# breakout.net
KiCad netlist of a schematic drawn in EAGLE
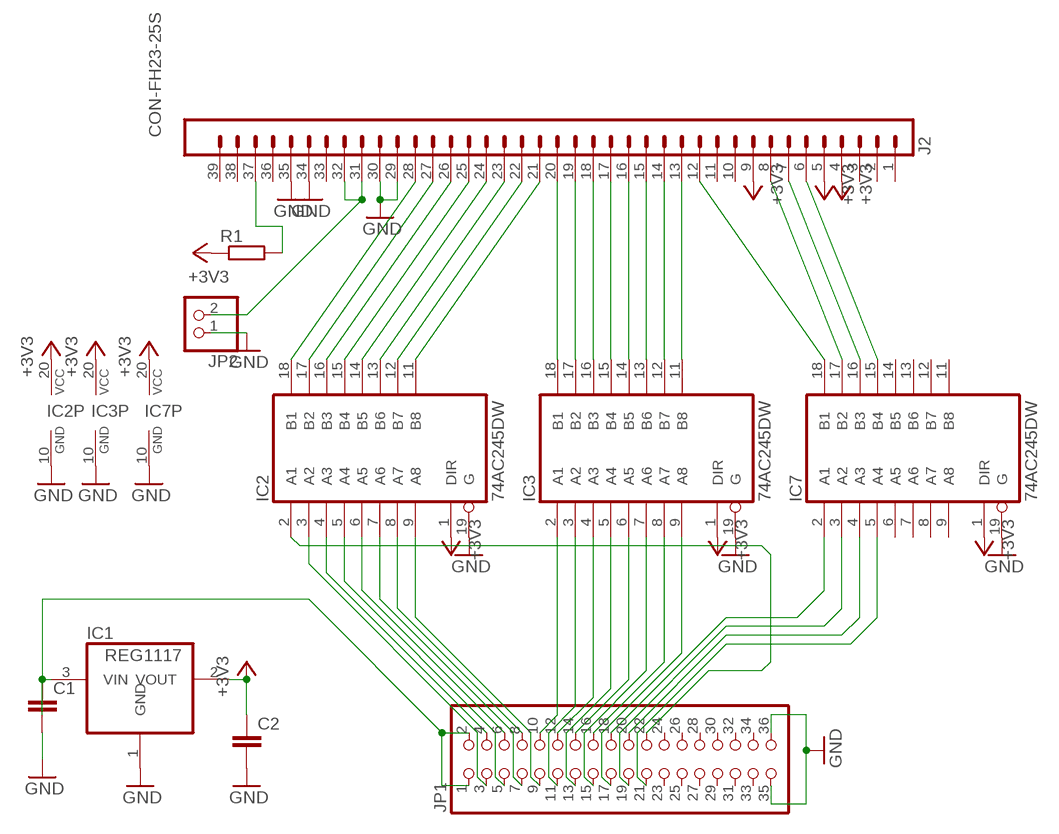
[diagram p0: schematic, sheet 1]

(export (version "E")
  (design (tool "Eeschema 10.0.6"))
  (components
    (comp (ref "C1")
      (value "C-EUC0805")
      (footprint "eagle-import:C0805")
      (libsource (lib "eagle-import") (part "C-EUC0805"))
    )
    (comp (ref "C2")
      (value "C-EUC0805")
      (footprint "eagle-import:C0805")
      (libsource (lib "eagle-import") (part "C-EUC0805"))
    )
    (comp (ref "IC1")
      (value "REG1117")
      (footprint "eagle-import:SOT223")
      (libsource (lib "eagle-import") (part "REG1117"))
    )
    (comp (ref "IC2")
      (value "74AC245DW")
      (footprint "eagle-import:SO20W")
      (libsource (lib "eagle-import") (part "74245DWAC"))
    )
    (comp (ref "IC3")
      (value "74AC245DW")
      (footprint "eagle-import:SO20W")
      (libsource (lib "eagle-import") (part "74245DWAC"))
    )
    (comp (ref "IC7")
      (value "74AC245DW")
      (footprint "eagle-import:SO20W")
      (libsource (lib "eagle-import") (part "74245DWAC"))
    )
    (comp (ref "J2")
      (value "CON-FH23-25S")
      (footprint "eagle-import:FH23-25S")
      (libsource (lib "eagle-import") (part "CON-FH23-25S"))
    )
    (comp (ref "JP1")
      (value "PINHD-2X18")
      (footprint "eagle-import:2X18")
      (libsource (lib "eagle-import") (part "PINHD-2X18"))
    )
    (comp (ref "JP2")
      (value "PINHD-1X2")
      (footprint "eagle-import:1X02")
      (libsource (lib "eagle-import") (part "PINHD-1X2"))
    )
    (comp (ref "R1")
      (value "R-EU_R0805")
      (footprint "eagle-import:R0805")
      (libsource (lib "eagle-import") (part "R-EU_R0805"))
    )
  )
  (nets
    (net (code "1") (name "+3V3") (class "Default")
      (node (ref "C2") (pin "1") (pinfunction "1_1") (pintype "passive"))
      (node (ref "IC1") (pin "2") (pinfunction "VOUT_2") (pintype "output"))
      (node (ref "IC2") (pin "1") (pinfunction "DIR_1") (pintype "input"))
      (node (ref "IC2") (pin "20") (pinfunction "VCC_20") (pintype "power_in"))
      (node (ref "IC3") (pin "1") (pinfunction "DIR_1") (pintype "input"))
      (node (ref "IC3") (pin "20") (pinfunction "VCC_20") (pintype "power_in"))
      (node (ref "IC7") (pin "1") (pinfunction "DIR_1") (pintype "input"))
      (node (ref "IC7") (pin "20") (pinfunction "VCC_20") (pintype "power_in"))
      (node (ref "J2") (pin "4") (pinfunction "4_4") (pintype "passive"))
      (node (ref "J2") (pin "5") (pinfunction "5_5") (pintype "passive"))
      (node (ref "J2") (pin "9") (pinfunction "9_9") (pintype "passive"))
      (node (ref "R1") (pin "1") (pinfunction "1_1") (pintype "passive"))
    )
    (net (code "2") (name "GND") (class "Default")
      (node (ref "C1") (pin "2") (pinfunction "2_2") (pintype "passive"))
      (node (ref "C2") (pin "2") (pinfunction "2_2") (pintype "passive"))
      (node (ref "IC1") (pin "1") (pinfunction "GND_1") (pintype "power_in"))
      (node (ref "IC2") (pin "10") (pinfunction "GND_10") (pintype "power_in"))
      (node (ref "IC2") (pin "19") (pinfunction "G_19") (pintype "input"))
      (node (ref "IC3") (pin "10") (pinfunction "GND_10") (pintype "power_in"))
      (node (ref "IC3") (pin "19") (pinfunction "G_19") (pintype "input"))
      (node (ref "IC7") (pin "10") (pinfunction "GND_10") (pintype "power_in"))
      (node (ref "IC7") (pin "19") (pinfunction "G_19") (pintype "input"))
      (node (ref "J2") (pin "29") (pinfunction "29_29") (pintype "passive"))
      (node (ref "J2") (pin "30") (pinfunction "30_30") (pintype "passive"))
      (node (ref "J2") (pin "34") (pinfunction "34_34") (pintype "passive"))
      (node (ref "J2") (pin "35") (pinfunction "35_35") (pintype "passive"))
      (node (ref "JP1") (pin "35") (pinfunction "35_35") (pintype "passive"))
      (node (ref "JP1") (pin "36") (pinfunction "36_36") (pintype "passive"))
      (node (ref "JP2") (pin "1") (pinfunction "1_1") (pintype "passive"))
    )
    (net (code "3") (name "Net-(IC1-VIN)") (class "Default")
      (node (ref "C1") (pin "1") (pinfunction "1_1") (pintype "passive"))
      (node (ref "IC1") (pin "3") (pinfunction "VIN_3") (pintype "input"))
      (node (ref "JP1") (pin "1") (pinfunction "1_1") (pintype "passive"))
      (node (ref "JP1") (pin "2") (pinfunction "2_2") (pintype "passive"))
    )
    (net (code "4") (name "Net-(IC2A-A1)") (class "Default")
      (node (ref "IC2") (pin "2") (pinfunction "A1_2") (pintype "bidirectional"))
      (node (ref "JP1") (pin "22") (pinfunction "22_22") (pintype "passive"))
    )
    (net (code "5") (name "Net-(IC2A-A2)") (class "Default")
      (node (ref "IC2") (pin "3") (pinfunction "A2_3") (pintype "bidirectional"))
      (node (ref "JP1") (pin "3") (pinfunction "3_3") (pintype "passive"))
    )
    (net (code "6") (name "Net-(IC2A-A3)") (class "Default")
      (node (ref "IC2") (pin "4") (pinfunction "A3_4") (pintype "bidirectional"))
      (node (ref "JP1") (pin "4") (pinfunction "4_4") (pintype "passive"))
    )
    (net (code "7") (name "Net-(IC2A-A4)") (class "Default")
      (node (ref "IC2") (pin "5") (pinfunction "A4_5") (pintype "bidirectional"))
      (node (ref "JP1") (pin "5") (pinfunction "5_5") (pintype "passive"))
    )
    (net (code "8") (name "Net-(IC2A-A5)") (class "Default")
      (node (ref "IC2") (pin "6") (pinfunction "A5_6") (pintype "bidirectional"))
      (node (ref "JP1") (pin "6") (pinfunction "6_6") (pintype "passive"))
    )
    (net (code "9") (name "Net-(IC2A-A6)") (class "Default")
      (node (ref "IC2") (pin "7") (pinfunction "A6_7") (pintype "bidirectional"))
      (node (ref "JP1") (pin "7") (pinfunction "7_7") (pintype "passive"))
    )
    (net (code "10") (name "Net-(IC2A-A7)") (class "Default")
      (node (ref "IC2") (pin "8") (pinfunction "A7_8") (pintype "bidirectional"))
      (node (ref "JP1") (pin "8") (pinfunction "8_8") (pintype "passive"))
    )
    (net (code "11") (name "Net-(IC2A-A8)") (class "Default")
      (node (ref "IC2") (pin "9") (pinfunction "A8_9") (pintype "bidirectional"))
      (node (ref "JP1") (pin "9") (pinfunction "9_9") (pintype "passive"))
    )
    (net (code "12") (name "Net-(IC2A-B1)") (class "Default")
      (node (ref "IC2") (pin "18") (pinfunction "B1_18") (pintype "bidirectional"))
      (node (ref "J2") (pin "28") (pinfunction "28_28") (pintype "passive"))
    )
    (net (code "13") (name "Net-(IC2A-B2)") (class "Default")
      (node (ref "IC2") (pin "17") (pinfunction "B2_17") (pintype "bidirectional"))
      (node (ref "J2") (pin "27") (pinfunction "27_27") (pintype "passive"))
    )
    (net (code "14") (name "Net-(IC2A-B3)") (class "Default")
      (node (ref "IC2") (pin "16") (pinfunction "B3_16") (pintype "bidirectional"))
      (node (ref "J2") (pin "26") (pinfunction "26_26") (pintype "passive"))
    )
    (net (code "15") (name "Net-(IC2A-B4)") (class "Default")
      (node (ref "IC2") (pin "15") (pinfunction "B4_15") (pintype "bidirectional"))
      (node (ref "J2") (pin "25") (pinfunction "25_25") (pintype "passive"))
    )
    (net (code "16") (name "Net-(IC2A-B5)") (class "Default")
      (node (ref "IC2") (pin "14") (pinfunction "B5_14") (pintype "bidirectional"))
      (node (ref "J2") (pin "24") (pinfunction "24_24") (pintype "passive"))
    )
    (net (code "17") (name "Net-(IC2A-B6)") (class "Default")
      (node (ref "IC2") (pin "13") (pinfunction "B6_13") (pintype "bidirectional"))
      (node (ref "J2") (pin "23") (pinfunction "23_23") (pintype "passive"))
    )
    (net (code "18") (name "Net-(IC2A-B7)") (class "Default")
      (node (ref "IC2") (pin "12") (pinfunction "B7_12") (pintype "bidirectional"))
      (node (ref "J2") (pin "22") (pinfunction "22_22") (pintype "passive"))
    )
    (net (code "19") (name "Net-(IC2A-B8)") (class "Default")
      (node (ref "IC2") (pin "11") (pinfunction "B8_11") (pintype "bidirectional"))
      (node (ref "J2") (pin "21") (pinfunction "21_21") (pintype "passive"))
    )
    (net (code "20") (name "Net-(IC3A-A1)") (class "Default")
      (node (ref "IC3") (pin "2") (pinfunction "A1_2") (pintype "bidirectional"))
      (node (ref "JP1") (pin "10") (pinfunction "10_10") (pintype "passive"))
    )
    (net (code "21") (name "Net-(IC3A-A2)") (class "Default")
      (node (ref "IC3") (pin "3") (pinfunction "A2_3") (pintype "bidirectional"))
      (node (ref "JP1") (pin "11") (pinfunction "11_11") (pintype "passive"))
    )
    (net (code "22") (name "Net-(IC3A-A3)") (class "Default")
      (node (ref "IC3") (pin "4") (pinfunction "A3_4") (pintype "bidirectional"))
      (node (ref "JP1") (pin "12") (pinfunction "12_12") (pintype "passive"))
    )
    (net (code "23") (name "Net-(IC3A-A4)") (class "Default")
      (node (ref "IC3") (pin "5") (pinfunction "A4_5") (pintype "bidirectional"))
      (node (ref "JP1") (pin "13") (pinfunction "13_13") (pintype "passive"))
    )
    (net (code "24") (name "Net-(IC3A-A5)") (class "Default")
      (node (ref "IC3") (pin "6") (pinfunction "A5_6") (pintype "bidirectional"))
      (node (ref "JP1") (pin "14") (pinfunction "14_14") (pintype "passive"))
    )
    (net (code "25") (name "Net-(IC3A-A6)") (class "Default")
      (node (ref "IC3") (pin "7") (pinfunction "A6_7") (pintype "bidirectional"))
      (node (ref "JP1") (pin "15") (pinfunction "15_15") (pintype "passive"))
    )
    (net (code "26") (name "Net-(IC3A-A7)") (class "Default")
      (node (ref "IC3") (pin "8") (pinfunction "A7_8") (pintype "bidirectional"))
      (node (ref "JP1") (pin "16") (pinfunction "16_16") (pintype "passive"))
    )
    (net (code "27") (name "Net-(IC3A-A8)") (class "Default")
      (node (ref "IC3") (pin "9") (pinfunction "A8_9") (pintype "bidirectional"))
      (node (ref "JP1") (pin "17") (pinfunction "17_17") (pintype "passive"))
    )
    (net (code "28") (name "Net-(IC3A-B1)") (class "Default")
      (node (ref "IC3") (pin "18") (pinfunction "B1_18") (pintype "bidirectional"))
      (node (ref "J2") (pin "20") (pinfunction "20_20") (pintype "passive"))
    )
    (net (code "29") (name "Net-(IC3A-B2)") (class "Default")
      (node (ref "IC3") (pin "17") (pinfunction "B2_17") (pintype "bidirectional"))
      (node (ref "J2") (pin "19") (pinfunction "19_19") (pintype "passive"))
    )
    (net (code "30") (name "Net-(IC3A-B3)") (class "Default")
      (node (ref "IC3") (pin "16") (pinfunction "B3_16") (pintype "bidirectional"))
      (node (ref "J2") (pin "18") (pinfunction "18_18") (pintype "passive"))
    )
    (net (code "31") (name "Net-(IC3A-B4)") (class "Default")
      (node (ref "IC3") (pin "15") (pinfunction "B4_15") (pintype "bidirectional"))
      (node (ref "J2") (pin "17") (pinfunction "17_17") (pintype "passive"))
    )
    (net (code "32") (name "Net-(IC3A-B5)") (class "Default")
      (node (ref "IC3") (pin "14") (pinfunction "B5_14") (pintype "bidirectional"))
      (node (ref "J2") (pin "16") (pinfunction "16_16") (pintype "passive"))
    )
    (net (code "33") (name "Net-(IC3A-B6)") (class "Default")
      (node (ref "IC3") (pin "13") (pinfunction "B6_13") (pintype "bidirectional"))
      (node (ref "J2") (pin "15") (pinfunction "15_15") (pintype "passive"))
    )
    (net (code "34") (name "Net-(IC3A-B7)") (class "Default")
      (node (ref "IC3") (pin "12") (pinfunction "B7_12") (pintype "bidirectional"))
      (node (ref "J2") (pin "14") (pinfunction "14_14") (pintype "passive"))
    )
    (net (code "35") (name "Net-(IC3A-B8)") (class "Default")
      (node (ref "IC3") (pin "11") (pinfunction "B8_11") (pintype "bidirectional"))
      (node (ref "J2") (pin "13") (pinfunction "13_13") (pintype "passive"))
    )
    (net (code "36") (name "Net-(IC7A-A1)") (class "Default")
      (node (ref "IC7") (pin "2") (pinfunction "A1_2") (pintype "bidirectional"))
      (node (ref "JP1") (pin "18") (pinfunction "18_18") (pintype "passive"))
    )
    (net (code "37") (name "Net-(IC7A-A2)") (class "Default")
      (node (ref "IC7") (pin "3") (pinfunction "A2_3") (pintype "bidirectional"))
      (node (ref "JP1") (pin "19") (pinfunction "19_19") (pintype "passive"))
    )
    (net (code "38") (name "Net-(IC7A-A3)") (class "Default")
      (node (ref "IC7") (pin "4") (pinfunction "A3_4") (pintype "bidirectional"))
      (node (ref "JP1") (pin "20") (pinfunction "20_20") (pintype "passive"))
    )
    (net (code "39") (name "Net-(IC7A-A4)") (class "Default")
      (node (ref "IC7") (pin "5") (pinfunction "A4_5") (pintype "bidirectional"))
      (node (ref "JP1") (pin "21") (pinfunction "21_21") (pintype "passive"))
    )
    (net (code "40") (name "Net-(IC7A-B1)") (class "Default")
      (node (ref "IC7") (pin "18") (pinfunction "B1_18") (pintype "bidirectional"))
      (node (ref "J2") (pin "12") (pinfunction "12_12") (pintype "passive"))
    )
    (net (code "41") (name "Net-(IC7A-B2)") (class "Default")
      (node (ref "IC7") (pin "17") (pinfunction "B2_17") (pintype "bidirectional"))
      (node (ref "J2") (pin "8") (pinfunction "8_8") (pintype "passive"))
    )
    (net (code "42") (name "Net-(IC7A-B3)") (class "Default")
      (node (ref "IC7") (pin "16") (pinfunction "B3_16") (pintype "bidirectional"))
      (node (ref "J2") (pin "7") (pinfunction "7_7") (pintype "passive"))
    )
    (net (code "43") (name "Net-(IC7A-B4)") (class "Default")
      (node (ref "IC7") (pin "15") (pinfunction "B4_15") (pintype "bidirectional"))
      (node (ref "J2") (pin "6") (pinfunction "6_6") (pintype "passive"))
    )
    (net (code "44") (name "Net-(J2-Pad31)") (class "Default")
      (node (ref "J2") (pin "31") (pinfunction "31_31") (pintype "passive"))
      (node (ref "J2") (pin "32") (pinfunction "32_32") (pintype "passive"))
      (node (ref "JP2") (pin "2") (pinfunction "2_2") (pintype "passive"))
    )
    (net (code "45") (name "Net-(J2-Pad37)") (class "Default")
      (node (ref "J2") (pin "37") (pinfunction "37_37") (pintype "passive"))
      (node (ref "R1") (pin "2") (pinfunction "2_2") (pintype "passive"))
    )
    (net (code "46") (name "unconnected-(IC7A-A5-Pad6)") (class "Default")
      (node (ref "IC7") (pin "6") (pinfunction "A5_6") (pintype "bidirectional"))
    )
    (net (code "47") (name "unconnected-(IC7A-A6-Pad7)") (class "Default")
      (node (ref "IC7") (pin "7") (pinfunction "A6_7") (pintype "bidirectional"))
    )
    (net (code "48") (name "unconnected-(IC7A-A7-Pad8)") (class "Default")
      (node (ref "IC7") (pin "8") (pinfunction "A7_8") (pintype "bidirectional"))
    )
    (net (code "49") (name "unconnected-(IC7A-A8-Pad9)") (class "Default")
      (node (ref "IC7") (pin "9") (pinfunction "A8_9") (pintype "bidirectional"))
    )
    (net (code "50") (name "unconnected-(IC7A-B5-Pad14)") (class "Default")
      (node (ref "IC7") (pin "14") (pinfunction "B5_14") (pintype "bidirectional"))
    )
    (net (code "51") (name "unconnected-(IC7A-B6-Pad13)") (class "Default")
      (node (ref "IC7") (pin "13") (pinfunction "B6_13") (pintype "bidirectional"))
    )
    (net (code "52") (name "unconnected-(IC7A-B7-Pad12)") (class "Default")
      (node (ref "IC7") (pin "12") (pinfunction "B7_12") (pintype "bidirectional"))
    )
    (net (code "53") (name "unconnected-(IC7A-B8-Pad11)") (class "Default")
      (node (ref "IC7") (pin "11") (pinfunction "B8_11") (pintype "bidirectional"))
    )
    (net (code "54") (name "unconnected-(J2-Pad1)") (class "Default")
      (node (ref "J2") (pin "1") (pinfunction "1_1") (pintype "passive"))
    )
    (net (code "55") (name "unconnected-(J2-Pad2)") (class "Default")
      (node (ref "J2") (pin "2") (pinfunction "2_2") (pintype "passive"))
    )
    (net (code "56") (name "unconnected-(J2-Pad3)") (class "Default")
      (node (ref "J2") (pin "3") (pinfunction "3_3") (pintype "passive"))
    )
    (net (code "57") (name "unconnected-(J2-Pad10)") (class "Default")
      (node (ref "J2") (pin "10") (pinfunction "10_10") (pintype "passive"))
    )
    (net (code "58") (name "unconnected-(J2-Pad11)") (class "Default")
      (node (ref "J2") (pin "11") (pinfunction "11_11") (pintype "passive"))
    )
    (net (code "59") (name "unconnected-(J2-Pad33)") (class "Default")
      (node (ref "J2") (pin "33") (pinfunction "33_33") (pintype "passive"))
    )
    (net (code "60") (name "unconnected-(J2-Pad36)") (class "Default")
      (node (ref "J2") (pin "36") (pinfunction "36_36") (pintype "passive"))
    )
    (net (code "61") (name "unconnected-(J2-Pad38)") (class "Default")
      (node (ref "J2") (pin "38") (pinfunction "38_38") (pintype "passive"))
    )
    (net (code "62") (name "unconnected-(J2-Pad39)") (class "Default")
      (node (ref "J2") (pin "39") (pinfunction "39_39") (pintype "passive"))
    )
    (net (code "63") (name "unconnected-(JP1-Pad23)") (class "Default")
      (node (ref "JP1") (pin "23") (pinfunction "23_23") (pintype "passive"))
    )
    (net (code "64") (name "unconnected-(JP1-Pad24)") (class "Default")
      (node (ref "JP1") (pin "24") (pinfunction "24_24") (pintype "passive"))
    )
    (net (code "65") (name "unconnected-(JP1-Pad25)") (class "Default")
      (node (ref "JP1") (pin "25") (pinfunction "25_25") (pintype "passive"))
    )
    (net (code "66") (name "unconnected-(JP1-Pad26)") (class "Default")
      (node (ref "JP1") (pin "26") (pinfunction "26_26") (pintype "passive"))
    )
    (net (code "67") (name "unconnected-(JP1-Pad27)") (class "Default")
      (node (ref "JP1") (pin "27") (pinfunction "27_27") (pintype "passive"))
    )
    (net (code "68") (name "unconnected-(JP1-Pad28)") (class "Default")
      (node (ref "JP1") (pin "28") (pinfunction "28_28") (pintype "passive"))
    )
    (net (code "69") (name "unconnected-(JP1-Pad29)") (class "Default")
      (node (ref "JP1") (pin "29") (pinfunction "29_29") (pintype "passive"))
    )
    (net (code "70") (name "unconnected-(JP1-Pad30)") (class "Default")
      (node (ref "JP1") (pin "30") (pinfunction "30_30") (pintype "passive"))
    )
    (net (code "71") (name "unconnected-(JP1-Pad31)") (class "Default")
      (node (ref "JP1") (pin "31") (pinfunction "31_31") (pintype "passive"))
    )
    (net (code "72") (name "unconnected-(JP1-Pad32)") (class "Default")
      (node (ref "JP1") (pin "32") (pinfunction "32_32") (pintype "passive"))
    )
    (net (code "73") (name "unconnected-(JP1-Pad33)") (class "Default")
      (node (ref "JP1") (pin "33") (pinfunction "33_33") (pintype "passive"))
    )
    (net (code "74") (name "unconnected-(JP1-Pad34)") (class "Default")
      (node (ref "JP1") (pin "34") (pinfunction "34_34") (pintype "passive"))
    )
  )
)
